# Mobile_device_sheet6_interfaces.net
KiCad netlist of a schematic drawn in Altium Designer
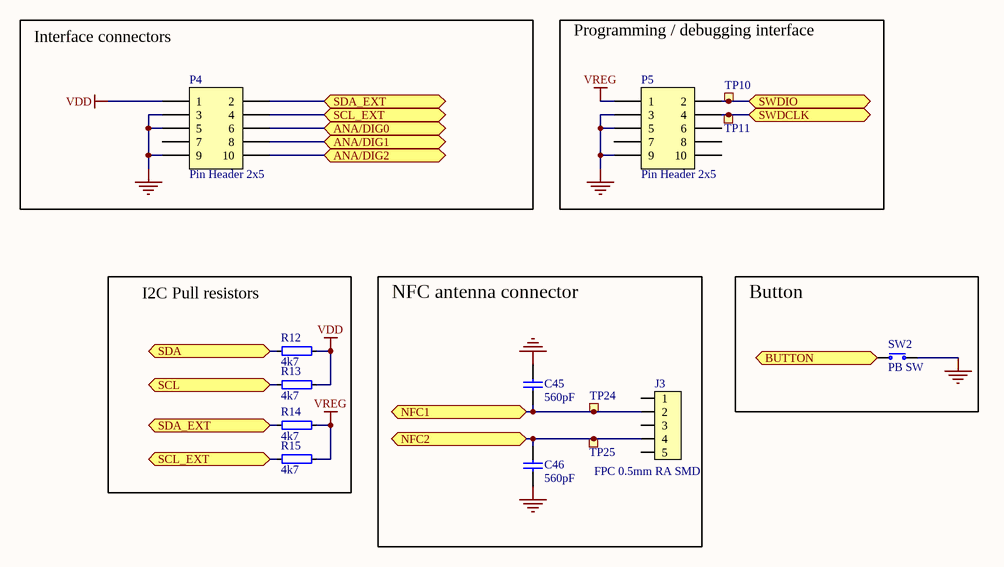
[diagram p0: Mobile_device_sheet6_interfaces.SchDoc]

(export (version "E")
  (design (tool "Eeschema 10.0.6"))
  (components
    (comp (ref "C45")
      (value "560pF")
      (footprint "CAPC1005X04L")
      (description "Capacitor, NP0, ±5%")
      (fields (field (name "PART NUMBER") "C0402-560p") (field (name "PUBLISHER") "Nordic Semiconductor"))
      (libsource (lib "Nordic Passive DB") (part "CAP"))
    )
    (comp (ref "C46")
      (value "560pF")
      (footprint "CAPC1005X04L")
      (description "Capacitor, NP0, ±5%")
      (fields (field (name "PART NUMBER") "C0402-560p") (field (name "PUBLISHER") "Nordic Semiconductor"))
      (libsource (lib "Nordic Passive DB") (part "CAP"))
    )
    (comp (ref "J3")
      (value "FPC 0.5mm RA SMD")
      (footprint "FPC_05P-0.5mm-RA-SMD")
      (description "0.5mm FPC, 5P,Right Angle SMT,Double Contact,H=1.2mm,White, Tin plated")
      (fields
        (field (name "PART NUMBER") "FPC_05P-0.5mm-RA-SMD")
        (field (name "MANUFACTURER") "W-CON")
        (field (name "PUBLISHER") "Nordic Semiconductor")
      )
      (libsource (lib "Nordic Passive DB") (part "CONN-5"))
    )
    (comp (ref "P4")
      (value "Pin Header 2x5")
      (footprint "HDR_2x5-SMD-1.27mm-ANG")
      (description "Pin Header 2x5, 1.27mm (50mil)")
      (fields
        (field (name "PART NUMBER") "Pin Header 2x5 SMD, 1.27mm, Angled")
        (field (name "MANUFACTURER") "Samtec")
        (field (name "PUBLISHER") "Nordic Semiconductor")
      )
      (libsource (lib "Nordic Passive DB") (part "CONN-2x5"))
    )
    (comp (ref "P5")
      (value "Pin Header 2x5")
      (footprint "HDR_2x5-SMD-1.27mm-ANG")
      (description "Pin Header 2x5, 1.27mm (50mil)")
      (fields
        (field (name "PART NUMBER") "Pin Header 2x5 SMD, 1.27mm, Angled")
        (field (name "MANUFACTURER") "Samtec")
        (field (name "PUBLISHER") "Nordic Semiconductor")
      )
      (libsource (lib "Nordic Passive DB") (part "CONN-2x5"))
    )
    (comp (ref "R12")
      (value "4k7")
      (footprint "RESC1005X04L")
      (description "Resistor, ±1%, 0.063W")
      (fields (field (name "PART NUMBER") "R0402-4k7") (field (name "PUBLISHER") "Nordic Semiconductor"))
      (libsource (lib "Nordic Passive DB") (part "RES_1"))
    )
    (comp (ref "R13")
      (value "4k7")
      (footprint "RESC1005X04L")
      (description "Resistor, ±1%, 0.063W")
      (fields (field (name "PART NUMBER") "R0402-4k7") (field (name "PUBLISHER") "Nordic Semiconductor"))
      (libsource (lib "Nordic Passive DB") (part "RES_1"))
    )
    (comp (ref "R14")
      (value "4k7")
      (footprint "RESC1005X04L")
      (description "Resistor, ±1%, 0.063W")
      (fields (field (name "PART NUMBER") "R0402-4k7") (field (name "PUBLISHER") "Nordic Semiconductor"))
      (libsource (lib "Nordic Passive DB") (part "RES_1"))
    )
    (comp (ref "R15")
      (value "4k7")
      (footprint "RESC1005X04L")
      (description "Resistor, ±1%, 0.063W")
      (fields (field (name "PART NUMBER") "R0402-4k7") (field (name "PUBLISHER") "Nordic Semiconductor"))
      (libsource (lib "Nordic Passive DB") (part "RES_1"))
    )
    (comp (ref "SW2")
      (value "PB SW")
      (footprint "Switch-PB-6.2x6.3mm-SMD")
      (description "Tactile Switch, SPNO, SMD, 160gf, 6.2x6.3x2.5mm")
      (fields
        (field (name "PART NUMBER") "Switch-PB-6.2x6.3mm-SMD")
        (field (name "MANUFACTURER") "Dailywell")
        (field (name "PUBLISHER") "Nordic Semiconductor")
      )
      (libsource (lib "Nordic Discrete DB") (part "SW-PB"))
    )
    (comp (ref "TP10")
      (value "Ø1.5mm,SMD")
      (footprint "TP_SMD_Ø1.5mm")
      (description "1.0mm circular SMD testpad")
      (fields
        (field (name "PART NUMBER") "TP_SMD_Ø1.5MM")
        (field (name "MANUFACTURER") "Nordic Semiconductor")
        (field (name "PUBLISHER") "Nordic Semiconductor")
      )
      (libsource (lib "Nordic Passive DB") (part "TESTPAD"))
    )
    (comp (ref "TP11")
      (value "Ø1.5mm,SMD")
      (footprint "TP_SMD_Ø1.5mm")
      (description "1.0mm circular SMD testpad")
      (fields
        (field (name "PART NUMBER") "TP_SMD_Ø1.5MM")
        (field (name "MANUFACTURER") "Nordic Semiconductor")
        (field (name "PUBLISHER") "Nordic Semiconductor")
      )
      (libsource (lib "") (part "TESTPAD_1"))
    )
    (comp (ref "TP24")
      (value "Ø1.0mm,SMD")
      (footprint "TP_SMD_Ø1.0mm")
      (description "1.0mm circular SMD testpad")
      (fields
        (field (name "PART NUMBER") "TP_SMD_Ø1.0MM")
        (field (name "MANUFACTURER") "Nordic Semiconductor")
        (field (name "PUBLISHER") "Nordic Semiconductor")
      )
      (libsource (lib "Nordic Passive DB") (part "TESTPAD"))
    )
    (comp (ref "TP25")
      (value "Ø1.0mm,SMD")
      (footprint "TP_SMD_Ø1.0mm")
      (description "1.0mm circular SMD testpad")
      (fields
        (field (name "PART NUMBER") "TP_SMD_Ø1.0MM")
        (field (name "MANUFACTURER") "Nordic Semiconductor")
        (field (name "PUBLISHER") "Nordic Semiconductor")
      )
      (libsource (lib "") (part "TESTPAD_1"))
    )
  )
  (nets
    (net (code "1") (name "/ANA{slash}DIG0") (class "Default")
      (node (ref "P4") (pin "6") (pinfunction "6_6") (pintype "passive"))
    )
    (net (code "2") (name "/ANA{slash}DIG1") (class "Default")
      (node (ref "P4") (pin "8") (pinfunction "8_8") (pintype "passive"))
    )
    (net (code "3") (name "/ANA{slash}DIG2") (class "Default")
      (node (ref "P4") (pin "10") (pinfunction "10_10") (pintype "passive"))
    )
    (net (code "4") (name "/BUTTON") (class "Default")
      (node (ref "SW2") (pin "2") (pinfunction "COM_2") (pintype "passive"))
    )
    (net (code "5") (name "/NFC1") (class "Default")
      (node (ref "C45") (pin "1") (pinfunction "1_1") (pintype "passive"))
      (node (ref "J3") (pin "2") (pinfunction "2_2") (pintype "passive"))
      (node (ref "TP24") (pin "1") (pinfunction "1_1") (pintype "passive"))
    )
    (net (code "6") (name "/NFC2") (class "Default")
      (node (ref "C46") (pin "2") (pinfunction "2_2") (pintype "passive"))
      (node (ref "J3") (pin "4") (pinfunction "4_4") (pintype "passive"))
      (node (ref "TP25") (pin "1") (pinfunction "1_1") (pintype "passive"))
    )
    (net (code "7") (name "/SCL") (class "Default")
      (node (ref "R13") (pin "2") (pinfunction "2_2") (pintype "passive"))
    )
    (net (code "8") (name "/SCL_EXT") (class "Default")
      (node (ref "P4") (pin "4") (pinfunction "4_4") (pintype "passive"))
      (node (ref "R15") (pin "2") (pinfunction "2_2") (pintype "passive"))
    )
    (net (code "9") (name "/SDA") (class "Default")
      (node (ref "R12") (pin "2") (pinfunction "2_2") (pintype "passive"))
    )
    (net (code "10") (name "/SDA_EXT") (class "Default")
      (node (ref "P4") (pin "2") (pinfunction "2_2") (pintype "passive"))
      (node (ref "R14") (pin "2") (pinfunction "2_2") (pintype "passive"))
    )
    (net (code "11") (name "/SWDCLK") (class "Default")
      (node (ref "P5") (pin "4") (pinfunction "4_4") (pintype "passive"))
      (node (ref "TP11") (pin "1") (pinfunction "1_1") (pintype "passive"))
    )
    (net (code "12") (name "/SWDIO") (class "Default")
      (node (ref "P5") (pin "2") (pinfunction "2_2") (pintype "passive"))
      (node (ref "TP10") (pin "1") (pinfunction "1_1") (pintype "passive"))
    )
    (net (code "13") (name "GND") (class "Default")
      (node (ref "C45") (pin "2") (pinfunction "2_2") (pintype "passive"))
      (node (ref "C46") (pin "1") (pinfunction "1_1") (pintype "passive"))
      (node (ref "P4") (pin "3") (pinfunction "3_3") (pintype "passive"))
      (node (ref "P4") (pin "5") (pinfunction "5_5") (pintype "passive"))
      (node (ref "P4") (pin "9") (pinfunction "9_9") (pintype "passive"))
      (node (ref "P5") (pin "3") (pinfunction "3_3") (pintype "passive"))
      (node (ref "P5") (pin "5") (pinfunction "5_5") (pintype "passive"))
      (node (ref "P5") (pin "9") (pinfunction "9_9") (pintype "passive"))
      (node (ref "SW2") (pin "1") (pinfunction "N.O_1") (pintype "passive"))
    )
    (net (code "14") (name "VDD") (class "Default")
      (node (ref "P4") (pin "1") (pinfunction "1_1") (pintype "passive"))
      (node (ref "R12") (pin "1") (pinfunction "1_1") (pintype "passive"))
      (node (ref "R13") (pin "1") (pinfunction "1_1") (pintype "passive"))
    )
    (net (code "15") (name "VREG") (class "Default")
      (node (ref "P5") (pin "1") (pinfunction "1_1") (pintype "passive"))
      (node (ref "R14") (pin "1") (pinfunction "1_1") (pintype "passive"))
      (node (ref "R15") (pin "1") (pinfunction "1_1") (pintype "passive"))
    )
    (net (code "16") (name "unconnected-(J3-Pad1)") (class "Default")
      (node (ref "J3") (pin "1") (pinfunction "1_1") (pintype "passive"))
    )
    (net (code "17") (name "unconnected-(J3-Pad3)") (class "Default")
      (node (ref "J3") (pin "3") (pinfunction "3_3") (pintype "passive"))
    )
    (net (code "18") (name "unconnected-(J3-Pad5)") (class "Default")
      (node (ref "J3") (pin "5") (pinfunction "5_5") (pintype "passive"))
    )
    (net (code "19") (name "unconnected-(P4-Pad7)") (class "Default")
      (node (ref "P4") (pin "7") (pinfunction "7_7") (pintype "passive"))
    )
    (net (code "20") (name "unconnected-(P5-Pad6)") (class "Default")
      (node (ref "P5") (pin "6") (pinfunction "6_6") (pintype "passive"))
    )
    (net (code "21") (name "unconnected-(P5-Pad7)") (class "Default")
      (node (ref "P5") (pin "7") (pinfunction "7_7") (pintype "passive"))
    )
    (net (code "22") (name "unconnected-(P5-Pad8)") (class "Default")
      (node (ref "P5") (pin "8") (pinfunction "8_8") (pintype "passive"))
    )
    (net (code "23") (name "unconnected-(P5-Pad10)") (class "Default")
      (node (ref "P5") (pin "10") (pinfunction "10_10") (pintype "passive"))
    )
  )
)
